# panda_interface_point.net
KiCad netlist of a schematic drawn in EAGLE
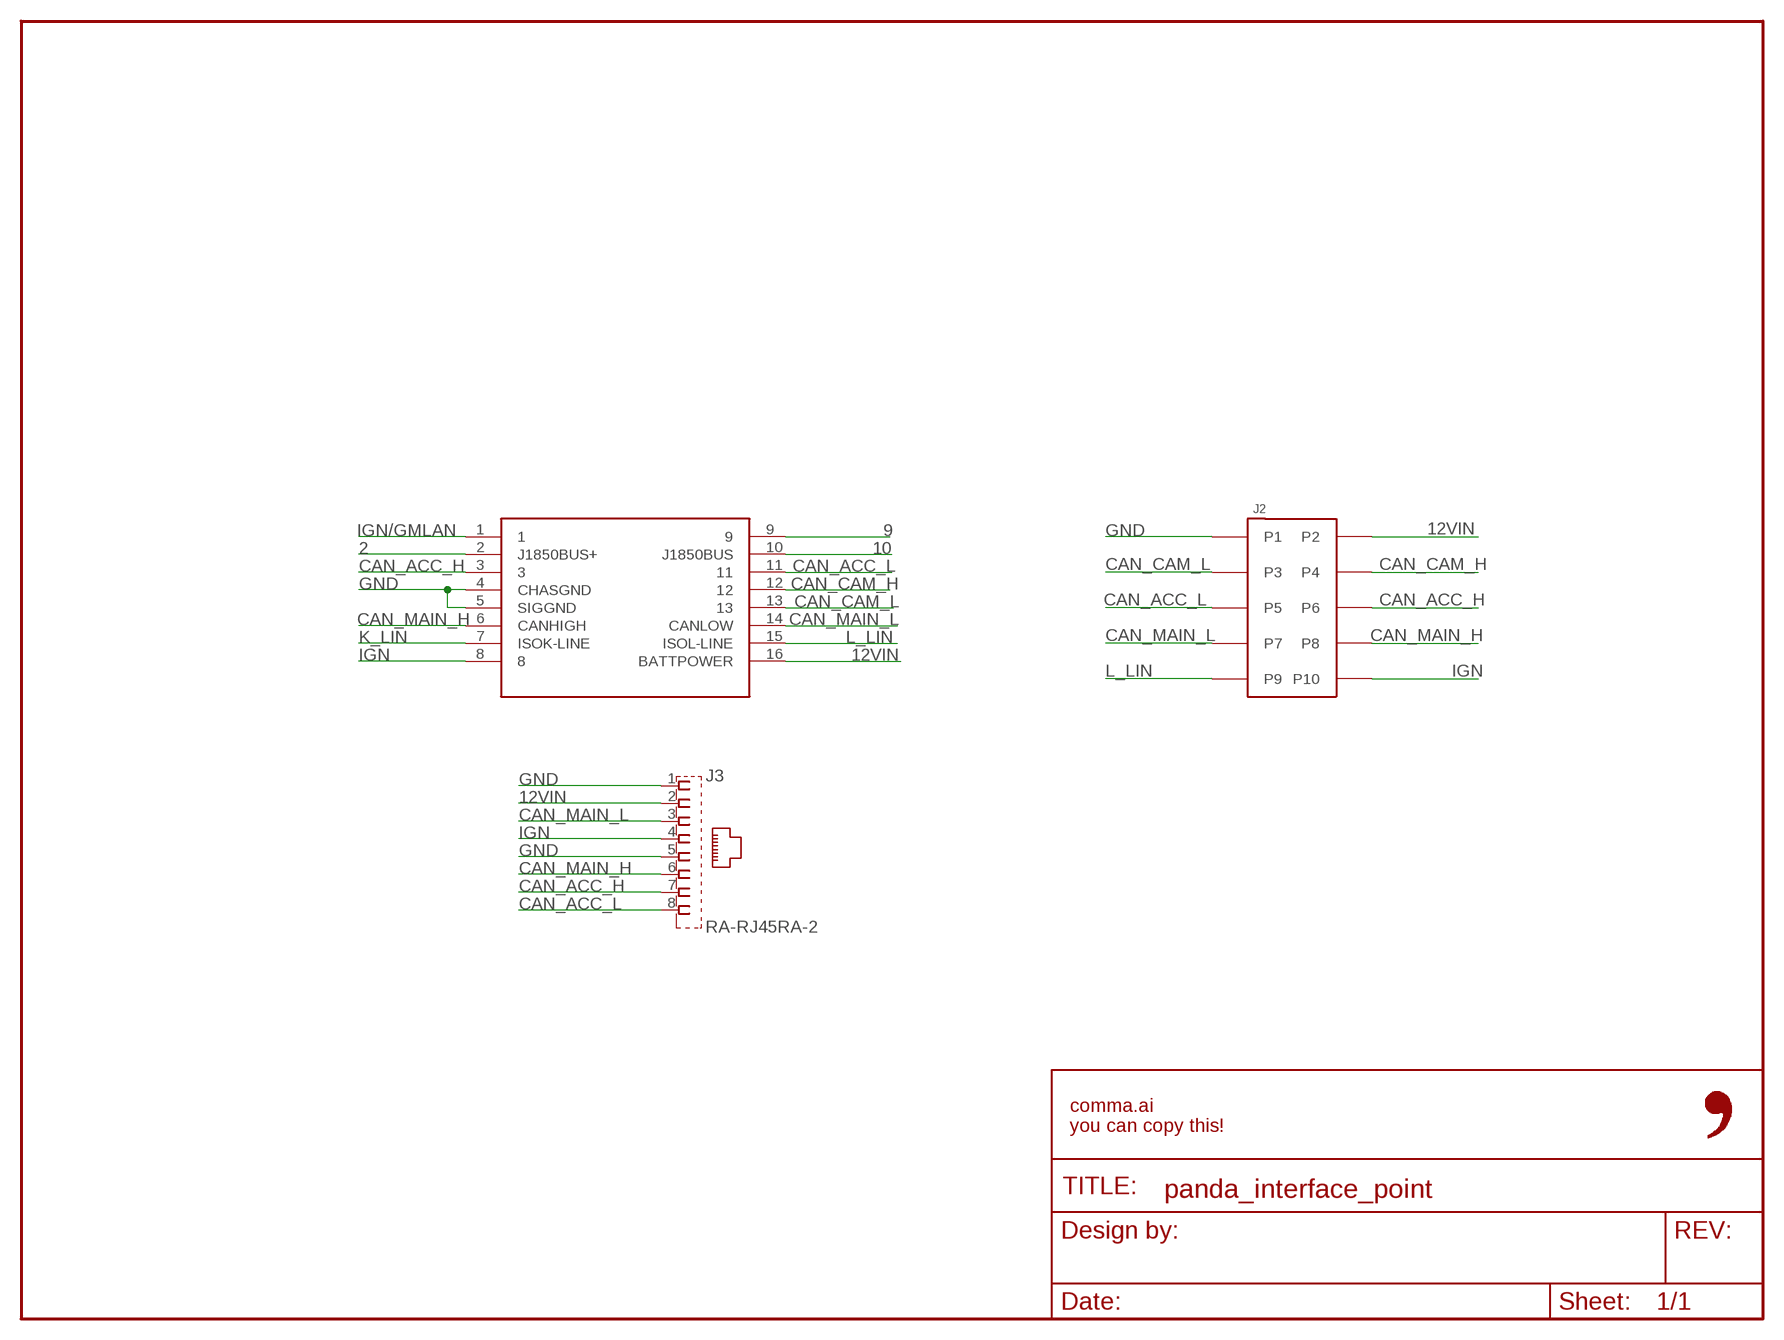
[diagram p0: schematic, sheet 1]

(export (version "E")
  (design (tool "Eeschema 10.0.6"))
  (components
    (comp (ref "FRAME1")
      (value "FRAME-LETTER-OPENNO_PACKAGE")
      (footprint "eagle-import:DUMMY")
      (fields (field (name "DESIGNER") "Nobody"))
      (libsource (lib "eagle-import") (part "FRAME-LETTER-OPENNO_PACKAGE"))
    )
    (comp (ref "J1")
      (value "OBDII-FEMALE-CUT")
      (footprint "eagle-import:OBDII-FEMALE-MIDCUT")
      (libsource (lib "eagle-import") (part "OBDII-FEMALE-CUT"))
    )
    (comp (ref "J2")
      (value "5018761040")
      (footprint "eagle-import:5018761040")
      (libsource (lib "eagle-import") (part "5018761040"))
    )
    (comp (ref "J3")
      (value "RA-RJ45RA-2")
      (footprint "eagle-import:RA-RJ45-2")
      (libsource (lib "eagle-import") (part "RA-RJ45RA-2"))
    )
  )
  (nets
    (net (code "1") (name "/2") (class "Default")
      (node (ref "J1") (pin "2") (pinfunction "J1850BUS+_2") (pintype "bidirectional"))
    )
    (net (code "2") (name "/9") (class "Default")
      (node (ref "J1") (pin "9") (pinfunction "9_9") (pintype "bidirectional"))
    )
    (net (code "3") (name "/10") (class "Default")
      (node (ref "J1") (pin "10") (pinfunction "J1850BUS_10") (pintype "bidirectional"))
    )
    (net (code "4") (name "/12VIN") (class "Default")
      (node (ref "J1") (pin "16") (pinfunction "BATTPOWER_16") (pintype "bidirectional"))
      (node (ref "J2") (pin "P2") (pinfunction "P2_P2") (pintype "bidirectional"))
      (node (ref "J3") (pin "2") (pinfunction "2_2") (pintype "passive"))
    )
    (net (code "5") (name "/CAN_ACC_H") (class "Default")
      (node (ref "J1") (pin "3") (pinfunction "3_3") (pintype "bidirectional"))
      (node (ref "J2") (pin "P6") (pinfunction "P6_P6") (pintype "bidirectional"))
      (node (ref "J3") (pin "7") (pinfunction "7_7") (pintype "passive"))
    )
    (net (code "6") (name "/CAN_ACC_L") (class "Default")
      (node (ref "J1") (pin "11") (pinfunction "11_11") (pintype "bidirectional"))
      (node (ref "J2") (pin "P5") (pinfunction "P5_P5") (pintype "bidirectional"))
      (node (ref "J3") (pin "8") (pinfunction "8_8") (pintype "passive"))
    )
    (net (code "7") (name "/CAN_CAM_H") (class "Default")
      (node (ref "J1") (pin "12") (pinfunction "12_12") (pintype "bidirectional"))
      (node (ref "J2") (pin "P4") (pinfunction "P4_P4") (pintype "bidirectional"))
    )
    (net (code "8") (name "/CAN_CAM_L") (class "Default")
      (node (ref "J1") (pin "13") (pinfunction "13_13") (pintype "bidirectional"))
      (node (ref "J2") (pin "P3") (pinfunction "P3_P3") (pintype "bidirectional"))
    )
    (net (code "9") (name "/CAN_MAIN_H") (class "Default")
      (node (ref "J1") (pin "6") (pinfunction "CANHIGH_6") (pintype "bidirectional"))
      (node (ref "J2") (pin "P8") (pinfunction "P8_P8") (pintype "bidirectional"))
      (node (ref "J3") (pin "6") (pinfunction "6_6") (pintype "passive"))
    )
    (net (code "10") (name "/CAN_MAIN_L") (class "Default")
      (node (ref "J1") (pin "14") (pinfunction "CANLOW_14") (pintype "bidirectional"))
      (node (ref "J2") (pin "P7") (pinfunction "P7_P7") (pintype "bidirectional"))
      (node (ref "J3") (pin "3") (pinfunction "3_3") (pintype "passive"))
    )
    (net (code "11") (name "/GND") (class "Default")
      (node (ref "J1") (pin "4") (pinfunction "CHASGND_4") (pintype "bidirectional"))
      (node (ref "J1") (pin "5") (pinfunction "SIGGND_5") (pintype "bidirectional"))
      (node (ref "J2") (pin "P1") (pinfunction "P1_P1") (pintype "bidirectional"))
      (node (ref "J3") (pin "1") (pinfunction "1_1") (pintype "passive"))
      (node (ref "J3") (pin "5") (pinfunction "5_5") (pintype "passive"))
    )
    (net (code "12") (name "/IGN") (class "Default")
      (node (ref "J1") (pin "8") (pinfunction "8_8") (pintype "bidirectional"))
      (node (ref "J2") (pin "P10") (pinfunction "P10_P10") (pintype "bidirectional"))
      (node (ref "J3") (pin "4") (pinfunction "4_4") (pintype "passive"))
    )
    (net (code "13") (name "/IGN{slash}GMLAN") (class "Default")
      (node (ref "J1") (pin "1") (pinfunction "1_1") (pintype "bidirectional"))
    )
    (net (code "14") (name "/K_LIN") (class "Default")
      (node (ref "J1") (pin "7") (pinfunction "ISOK-LINE_7") (pintype "bidirectional"))
    )
    (net (code "15") (name "/L_LIN") (class "Default")
      (node (ref "J1") (pin "15") (pinfunction "ISOL-LINE_15") (pintype "bidirectional"))
      (node (ref "J2") (pin "P9") (pinfunction "P9_P9") (pintype "bidirectional"))
    )
  )
)
